# SIM800.net
KiCad netlist of a schematic drawn in Altium Designer
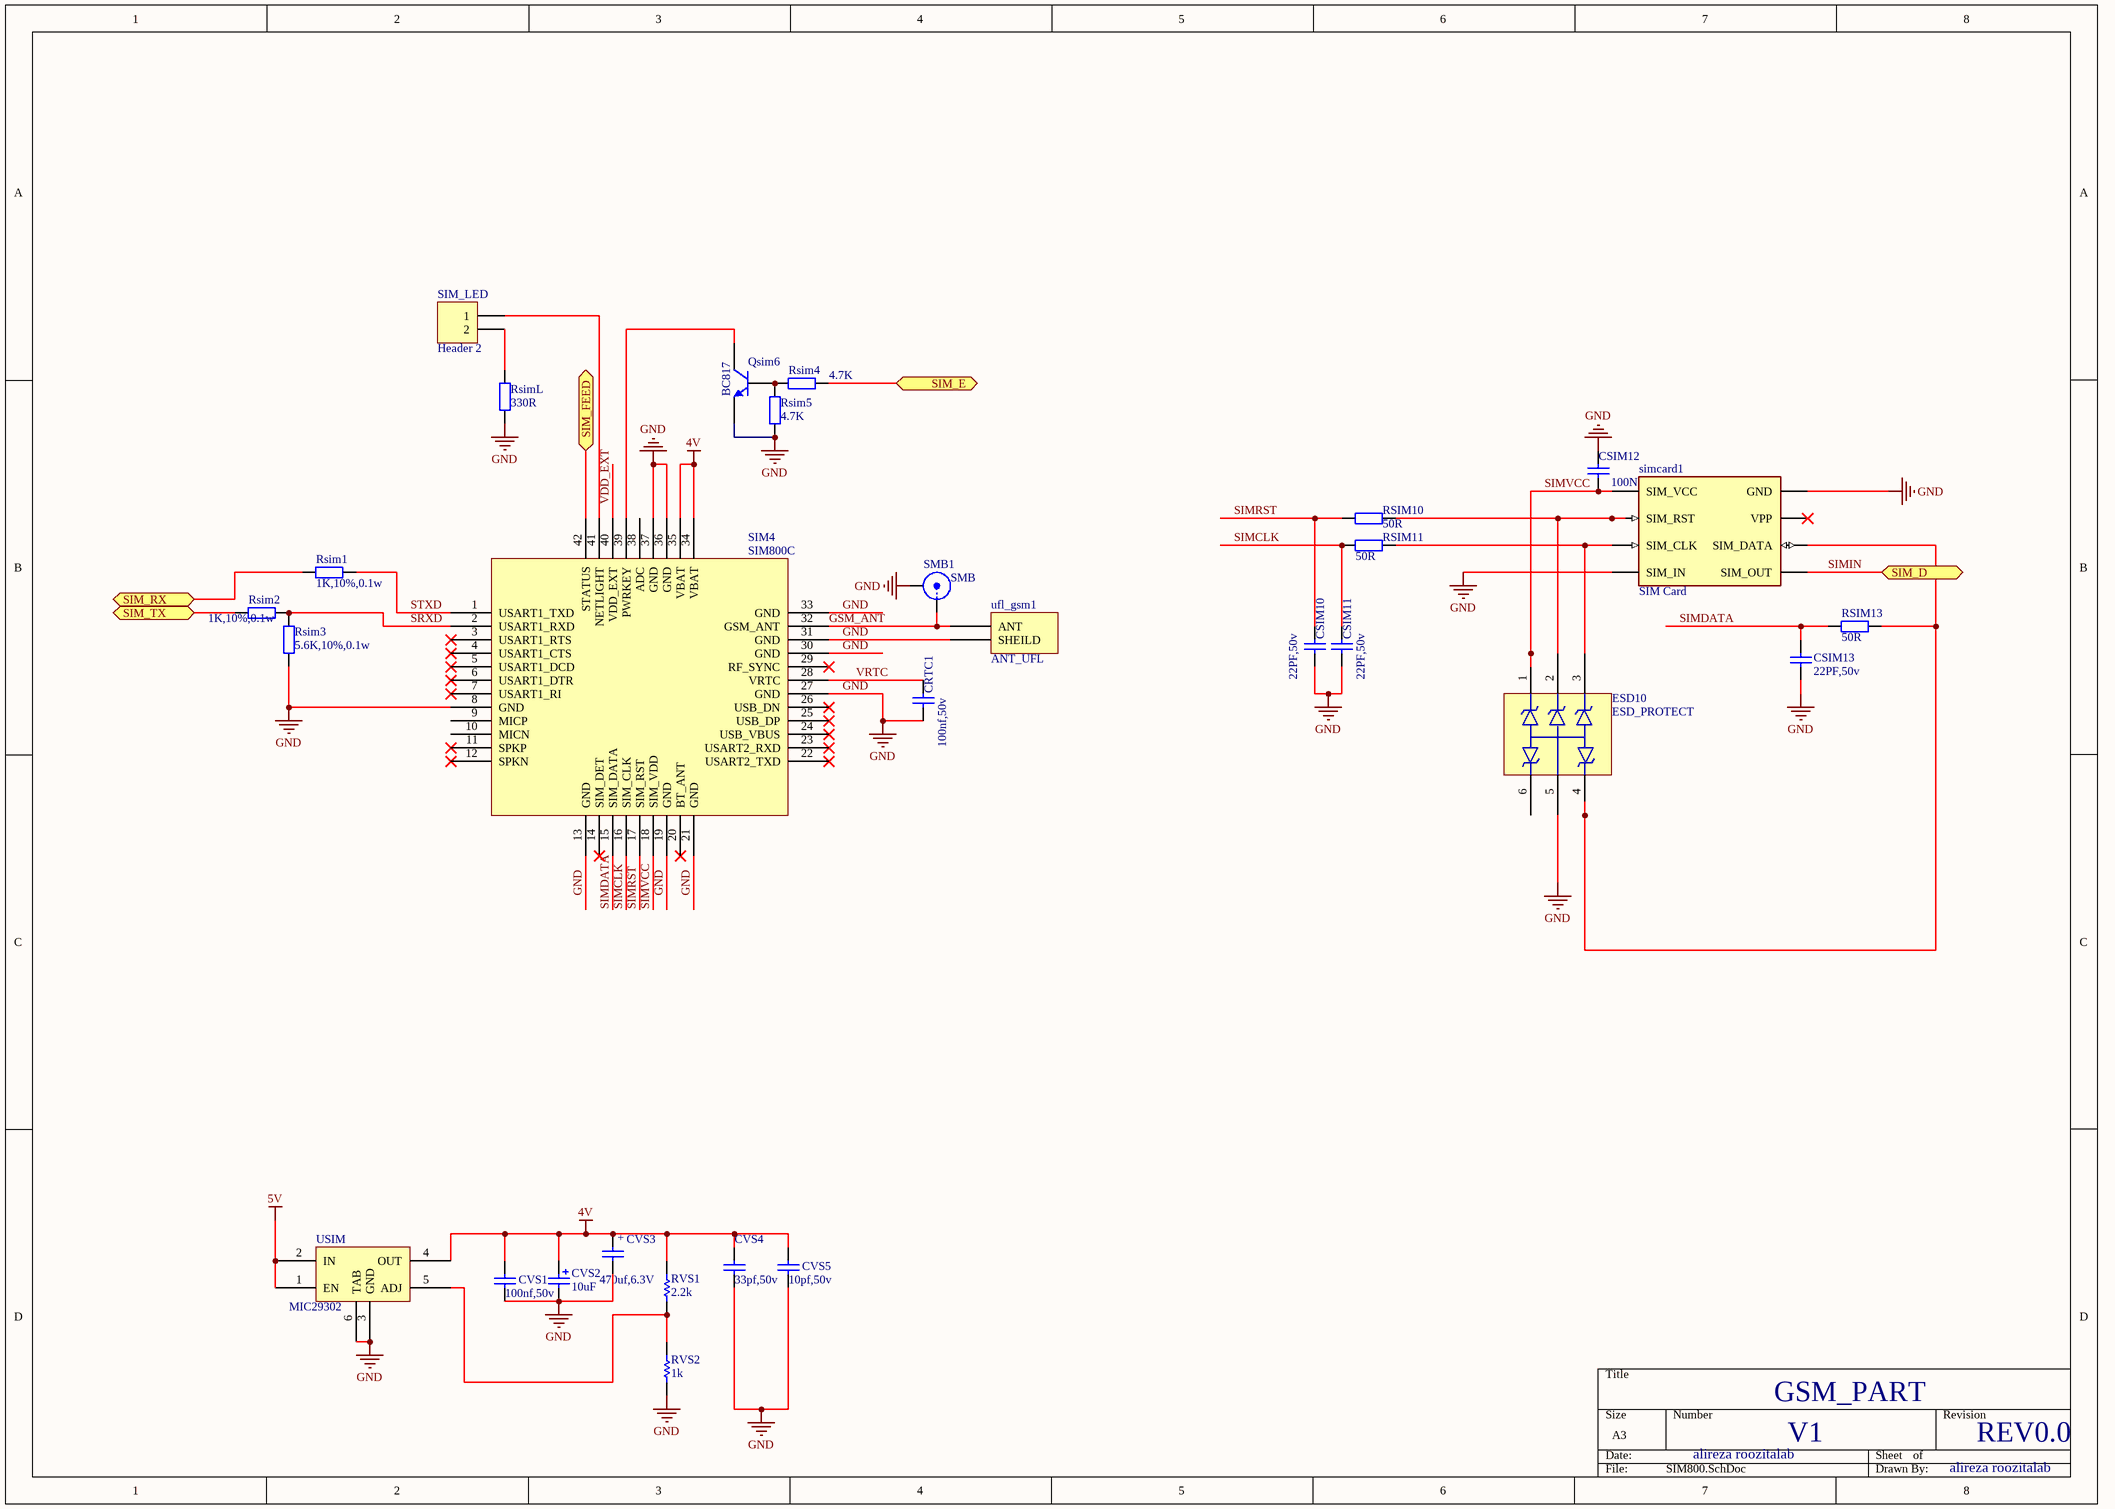
[diagram p0: SIM800.SchDoc]

(export (version "E")
  (design (tool "Eeschema 10.0.6"))
  (components
    (comp (ref "CRTC1")
      (value "100nf,50v")
      (footprint "0805.")
      (description "Capacitor")
      (fields (field (name "PUBLISHER") "Altium Limited"))
      (libsource (lib "MBIO-SCHPCB-MBFD-REV1") (part "Cap"))
    )
    (comp (ref "CSIM10")
      (value "22PF,50v")
      (footprint "0805.")
      (description "Capacitor")
      (fields (field (name "PUBLISHER") "Altium Limited"))
      (libsource (lib "MBIO-SCHPCB-MBFD-REV1") (part "Cap"))
    )
    (comp (ref "CSIM11")
      (value "22PF,50v")
      (footprint "0805.")
      (description "Capacitor")
      (fields (field (name "PUBLISHER") "Altium Limited"))
      (libsource (lib "MBIO-SCHPCB-MBFD-REV1") (part "Cap"))
    )
    (comp (ref "CSIM12")
      (value "100N")
      (footprint "0805.")
      (description "Capacitor")
      (fields (field (name "PUBLISHER") "Altium Limited"))
      (libsource (lib "MBIO-SCHPCB-MBFD-REV1") (part "Cap"))
    )
    (comp (ref "CSIM13")
      (value "22PF,50v")
      (footprint "0805.")
      (description "Capacitor")
      (fields (field (name "PUBLISHER") "Altium Limited"))
      (libsource (lib "MBIO-SCHPCB-MBFD-REV1") (part "Cap"))
    )
    (comp (ref "CVS1")
      (value "100nf,50v")
      (footprint "0805.")
      (description "Capacitor")
      (fields (field (name "PUBLISHER") "Altium Limited"))
      (libsource (lib "MBIO-SCHPCB-MBFD-REV1") (part "Cap"))
    )
    (comp (ref "CVS2")
      (value "10uF")
      (footprint "C1206.")
      (description "Polarized Capacitor (Radial)")
      (fields (field (name "PUBLISHER") "Altium Limited"))
      (libsource (lib "PCB_Project1") (part "Cap Pol1"))
    )
    (comp (ref "CVS3")
      (value "470uf,6.3V")
      (footprint "MY_SMC_D")
      (description "Polar capacitor")
      (fields (field (name "ASID PART NUMBER") "C-AS"))
      (libsource (lib "TPS54331") (part "Cap Pol"))
    )
    (comp (ref "CVS4")
      (value "33pf,50v")
      (footprint "0805.")
      (description "Capacitor")
      (fields (field (name "PUBLISHER") "Altium Limited"))
      (libsource (lib "MBIO-SCHPCB-MBFD-REV1") (part "Cap"))
    )
    (comp (ref "CVS5")
      (value "10pf,50v")
      (footprint "0805.")
      (description "Capacitor")
      (fields (field (name "PUBLISHER") "Altium Limited"))
      (libsource (lib "MBIO-SCHPCB-MBFD-REV1") (part "Cap"))
    )
    (comp (ref "ESD10")
      (value "ESD_PROTECT")
      (footprint "SMF05")
      (libsource (lib "armlib") (part "ESD_PROTECT"))
    )
    (comp (ref "Qsim6")
      (value "BC817")
      (footprint "2N3906_SMD")
      (description "NPN General Purpose Amplifier")
      (fields (field (name "PUBLISHER") "Altium Limited"))
      (libsource (lib "Miscellaneous Devices") (part "2N3904"))
    )
    (comp (ref "Rsim1")
      (value "1K,10%,0.1w")
      (footprint "0805.")
      (description "Resistor")
      (fields (field (name "PUBLISHER") "Altium Limited"))
      (libsource (lib "") (part "Res2_3"))
    )
    (comp (ref "Rsim2")
      (value "1K,10%,0.1w")
      (footprint "0805.")
      (description "Resistor")
      (fields (field (name "PUBLISHER") "Altium Limited"))
      (libsource (lib "") (part "Res2_1"))
    )
    (comp (ref "Rsim3")
      (value "5.6K,10%,0.1w")
      (footprint "0805.")
      (description "Resistor")
      (fields (field (name "PUBLISHER") "Altium Limited"))
      (libsource (lib "MBIO-SCHPCB-MBFD-REV1") (part "Res2"))
    )
    (comp (ref "Rsim4")
      (value "4.7K")
      (footprint "0805.")
      (description "Resistor")
      (fields (field (name "Comment") "10K,10%,0.1w") (field (name "PUBLISHER") "Altium Limited"))
      (libsource (lib "") (part "Res2_2"))
    )
    (comp (ref "Rsim5")
      (value "4.7K")
      (footprint "0805.")
      (description "Resistor")
      (fields (field (name "Comment") "10K,10%,0.1w") (field (name "PUBLISHER") "Altium Limited"))
      (libsource (lib "") (part "Res2_1"))
    )
    (comp (ref "RSIM10")
      (value "50R")
      (footprint "0805.")
      (description "Resistor")
      (fields (field (name "Comment") "47R,10%,0.1w") (field (name "PUBLISHER") "Altium Limited"))
      (libsource (lib "PCB_Project1") (part "Res2"))
    )
    (comp (ref "RSIM11")
      (value "50R")
      (footprint "0805.")
      (description "Resistor")
      (fields (field (name "Comment") "47R,10%,0.1w") (field (name "PUBLISHER") "Altium Limited"))
      (libsource (lib "PCB_Project1") (part "Res2"))
    )
    (comp (ref "RSIM13")
      (value "50R")
      (footprint "0805.")
      (description "Resistor")
      (fields (field (name "Comment") "47R,10%,0.1w") (field (name "PUBLISHER") "Altium Limited"))
      (libsource (lib "PCB_Project1") (part "Res2"))
    )
    (comp (ref "RsimL")
      (value "330R")
      (footprint "0805.")
      (description "Resistor")
      (fields (field (name "Comment") "330R,10%,0.1w") (field (name "PUBLISHER") "Altium Limited"))
      (libsource (lib "") (part "Res2_1"))
    )
    (comp (ref "RVS1")
      (value "2.2k")
      (footprint "0805.")
      (description "Resistor")
      (fields (field (name "PUBLISHER") "Altium Limited"))
      (libsource (lib "PCB_Project1") (part "Res1"))
    )
    (comp (ref "RVS2")
      (value "1k")
      (footprint "0805.")
      (description "Resistor")
      (fields (field (name "PUBLISHER") "Altium Limited"))
      (libsource (lib "PCB_Project1") (part "Res1"))
    )
    (comp (ref "SIM4") (value "SIM800C") (footprint "SIM800C") (libsource (lib "armlib") (part "SIM800C")))
    (comp (ref "simcard1")
      (value "SIM Card")
      (footprint "MY_SIMCARD")
      (description "Sim Card")
      (libsource (lib "Mylib") (part "SIM Card"))
    )
    (comp (ref "SIM_LED")
      (value "Header 2")
      (footprint "HDR1X2")
      (description "Header, 2-Pin")
      (fields (field (name "PUBLISHER") "Altium Limited"))
      (libsource (lib "Miscellaneous Connectors") (part "Header 2"))
    )
    (comp (ref "SMB1")
      (value "SMB")
      (footprint "SMB_V-RJ45")
      (description "SMB Straight Connector")
      (fields (field (name "PUBLISHER") "Altium Limited"))
      (libsource (lib "Miscellaneous Connectors") (part "SMB"))
    )
    (comp (ref "ufl_gsm1")
      (value "ANT_UFL")
      (footprint "UFL_CON")
      (libsource (lib "armlib") (part "ANT_UFL"))
    )
    (comp (ref "USIM") (value "MIC29302") (footprint "MIC29302") (libsource (lib "armlib") (part "MIC29302")))
  )
  (nets
    (net (code "1") (name "/GSM_ANT") (class "Default")
      (node (ref "SIM4") (pin "32") (pinfunction "GSM_ANT_32") (pintype "passive"))
      (node (ref "SMB1") (pin "1") (pinfunction "X_1") (pintype "passive"))
      (node (ref "ufl_gsm1") (pin "2") (pinfunction "ANT_2") (pintype "passive"))
    )
    (net (code "2") (name "/SIMCLK") (class "Default")
      (node (ref "CSIM11") (pin "2") (pinfunction "2_2") (pintype "passive"))
      (node (ref "RSIM11") (pin "1") (pinfunction "1_1") (pintype "passive"))
      (node (ref "SIM4") (pin "16") (pinfunction "SIM_CLK_16") (pintype "passive"))
    )
    (net (code "3") (name "/SIMDATA") (class "Default")
      (node (ref "CSIM13") (pin "2") (pinfunction "2_2") (pintype "passive"))
      (node (ref "RSIM13") (pin "1") (pinfunction "1_1") (pintype "passive"))
      (node (ref "SIM4") (pin "15") (pinfunction "SIM_DATA_15") (pintype "passive"))
    )
    (net (code "4") (name "/SIMIN") (class "Default")
      (node (ref "simcard1") (pin "C8") (pinfunction "SIM_OUT_C8") (pintype "passive"))
    )
    (net (code "5") (name "/SIMRST") (class "Default")
      (node (ref "CSIM10") (pin "2") (pinfunction "2_2") (pintype "passive"))
      (node (ref "RSIM10") (pin "1") (pinfunction "1_1") (pintype "passive"))
      (node (ref "SIM4") (pin "17") (pinfunction "SIM_RST_17") (pintype "passive"))
    )
    (net (code "6") (name "/SIMVCC") (class "Default")
      (node (ref "CSIM12") (pin "1") (pinfunction "1_1") (pintype "passive"))
      (node (ref "ESD10") (pin "1") (pinfunction "1_1") (pintype "passive"))
      (node (ref "SIM4") (pin "18") (pinfunction "SIM_VDD_18") (pintype "passive"))
      (node (ref "simcard1") (pin "C1") (pinfunction "SIM_VCC_C1") (pintype "power_in"))
    )
    (net (code "7") (name "/SIM_E") (class "Default")
      (node (ref "Rsim4") (pin "1") (pinfunction "1_1") (pintype "passive"))
    )
    (net (code "8") (name "/SIM_FEED") (class "Default")
      (node (ref "SIM4") (pin "42") (pinfunction "STATUS_42") (pintype "passive"))
    )
    (net (code "9") (name "/SIM_RX") (class "Default")
      (node (ref "Rsim1") (pin "2") (pinfunction "2_2") (pintype "passive"))
    )
    (net (code "10") (name "/SIM_TX") (class "Default")
      (node (ref "Rsim2") (pin "1") (pinfunction "1_1") (pintype "passive"))
    )
    (net (code "11") (name "/SRXD") (class "Default")
      (node (ref "Rsim2") (pin "2") (pinfunction "2_2") (pintype "passive"))
      (node (ref "Rsim3") (pin "2") (pinfunction "2_2") (pintype "passive"))
      (node (ref "SIM4") (pin "2") (pinfunction "USART1_RXD_2") (pintype "passive"))
    )
    (net (code "12") (name "/STXD") (class "Default")
      (node (ref "Rsim1") (pin "1") (pinfunction "1_1") (pintype "passive"))
      (node (ref "SIM4") (pin "1") (pinfunction "USART1_TXD_1") (pintype "passive"))
    )
    (net (code "13") (name "/VDD_EXT") (class "Default")
      (node (ref "SIM4") (pin "40") (pinfunction "VDD_EXT_40") (pintype "passive"))
    )
    (net (code "14") (name "/VRTC") (class "Default")
      (node (ref "CRTC1") (pin "2") (pinfunction "2_2") (pintype "passive"))
      (node (ref "SIM4") (pin "28") (pinfunction "VRTC_28") (pintype "passive"))
    )
    (net (code "15") (name "4V") (class "Default")
      (node (ref "CVS1") (pin "2") (pinfunction "2_2") (pintype "passive"))
      (node (ref "CVS2") (pin "1") (pinfunction "1_1") (pintype "passive"))
      (node (ref "CVS3") (pin "+") (pinfunction "+_+") (pintype "passive"))
      (node (ref "CVS4") (pin "2") (pinfunction "2_2") (pintype "passive"))
      (node (ref "CVS5") (pin "2") (pinfunction "2_2") (pintype "passive"))
      (node (ref "RVS1") (pin "2") (pinfunction "2_2") (pintype "passive"))
      (node (ref "SIM4") (pin "34") (pinfunction "VBAT_34") (pintype "passive"))
      (node (ref "SIM4") (pin "35") (pinfunction "VBAT_35") (pintype "passive"))
      (node (ref "USIM") (pin "4") (pinfunction "OUT_4") (pintype "passive"))
    )
    (net (code "16") (name "5V") (class "Default")
      (node (ref "USIM") (pin "1") (pinfunction "EN_1") (pintype "passive"))
      (node (ref "USIM") (pin "2") (pinfunction "IN_2") (pintype "passive"))
    )
    (net (code "17") (name "GND") (class "Default")
      (node (ref "CRTC1") (pin "1") (pinfunction "1_1") (pintype "passive"))
      (node (ref "CSIM10") (pin "1") (pinfunction "1_1") (pintype "passive"))
      (node (ref "CSIM11") (pin "1") (pinfunction "1_1") (pintype "passive"))
      (node (ref "CSIM12") (pin "2") (pinfunction "2_2") (pintype "passive"))
      (node (ref "CSIM13") (pin "1") (pinfunction "1_1") (pintype "passive"))
      (node (ref "CVS1") (pin "1") (pinfunction "1_1") (pintype "passive"))
      (node (ref "CVS2") (pin "2") (pinfunction "2_2") (pintype "passive"))
      (node (ref "CVS3") (pin "-") (pinfunction "-_-") (pintype "passive"))
      (node (ref "CVS4") (pin "1") (pinfunction "1_1") (pintype "passive"))
      (node (ref "CVS5") (pin "1") (pinfunction "1_1") (pintype "passive"))
      (node (ref "ESD10") (pin "5") (pinfunction "5_5") (pintype "passive"))
      (node (ref "Qsim6") (pin "1") (pinfunction "E_1") (pintype "passive"))
      (node (ref "RVS2") (pin "1") (pinfunction "1_1") (pintype "passive"))
      (node (ref "Rsim3") (pin "1") (pinfunction "1_1") (pintype "passive"))
      (node (ref "Rsim5") (pin "1") (pinfunction "1_1") (pintype "passive"))
      (node (ref "RsimL") (pin "1") (pinfunction "1_1") (pintype "passive"))
      (node (ref "SIM4") (pin "13") (pinfunction "GND_13") (pintype "passive"))
      (node (ref "SIM4") (pin "19") (pinfunction "GND_19") (pintype "passive"))
      (node (ref "SIM4") (pin "21") (pinfunction "GND_21") (pintype "passive"))
      (node (ref "SIM4") (pin "27") (pinfunction "GND_27") (pintype "passive"))
      (node (ref "SIM4") (pin "30") (pinfunction "GND_30") (pintype "passive"))
      (node (ref "SIM4") (pin "31") (pinfunction "GND_31") (pintype "passive"))
      (node (ref "SIM4") (pin "33") (pinfunction "GND_33") (pintype "passive"))
      (node (ref "SIM4") (pin "36") (pinfunction "GND_36") (pintype "passive"))
      (node (ref "SIM4") (pin "37") (pinfunction "GND_37") (pintype "passive"))
      (node (ref "SIM4") (pin "8") (pinfunction "GND_8") (pintype "passive"))
      (node (ref "SMB1") (pin "2") (pinfunction "Y_2") (pintype "passive"))
      (node (ref "USIM") (pin "3") (pinfunction "GND_3") (pintype "passive"))
      (node (ref "USIM") (pin "6") (pinfunction "TAB_6") (pintype "passive"))
      (node (ref "simcard1") (pin "C4") (pinfunction "SIM_IN_C4") (pintype "passive"))
      (node (ref "simcard1") (pin "C5") (pinfunction "GND_C5") (pintype "power_in"))
      (node (ref "ufl_gsm1") (pin "1") (pinfunction "SHEILD_1") (pintype "passive"))
    )
    (net (code "18") (name "Net-(Qsim6-B)") (class "Default")
      (node (ref "Qsim6") (pin "2") (pinfunction "B_2") (pintype "passive"))
      (node (ref "Rsim4") (pin "2") (pinfunction "2_2") (pintype "passive"))
      (node (ref "Rsim5") (pin "2") (pinfunction "2_2") (pintype "passive"))
    )
    (net (code "19") (name "Net-(Qsim6-C)") (class "Default")
      (node (ref "Qsim6") (pin "3") (pinfunction "C_3") (pintype "passive"))
      (node (ref "SIM4") (pin "39") (pinfunction "PWRKEY_39") (pintype "passive"))
    )
    (net (code "20") (name "Net-(RsimL-Pad2)") (class "Default")
      (node (ref "RsimL") (pin "2") (pinfunction "2_2") (pintype "passive"))
      (node (ref "SIM_LED") (pin "2") (pinfunction "2_2") (pintype "passive"))
    )
    (net (code "21") (name "Net-(SIM4-NETLIGHT)") (class "Default")
      (node (ref "SIM4") (pin "41") (pinfunction "NETLIGHT_41") (pintype "passive"))
      (node (ref "SIM_LED") (pin "1") (pinfunction "1_1") (pintype "passive"))
    )
    (net (code "22") (name "Net-(USIM-ADJ)") (class "Default")
      (node (ref "RVS1") (pin "1") (pinfunction "1_1") (pintype "passive"))
      (node (ref "RVS2") (pin "2") (pinfunction "2_2") (pintype "passive"))
      (node (ref "USIM") (pin "5") (pinfunction "ADJ_5") (pintype "passive"))
    )
    (net (code "23") (name "Net-(simcard1-SIM_CLK)") (class "Default")
      (node (ref "ESD10") (pin "3") (pinfunction "3_3") (pintype "passive"))
      (node (ref "RSIM11") (pin "2") (pinfunction "2_2") (pintype "passive"))
      (node (ref "simcard1") (pin "C3") (pinfunction "SIM_CLK_C3") (pintype "input"))
    )
    (net (code "24") (name "Net-(simcard1-SIM_DATA)") (class "Default")
      (node (ref "ESD10") (pin "4") (pinfunction "4_4") (pintype "passive"))
      (node (ref "RSIM13") (pin "2") (pinfunction "2_2") (pintype "passive"))
      (node (ref "simcard1") (pin "C7") (pinfunction "SIM_DATA_C7") (pintype "bidirectional"))
    )
    (net (code "25") (name "Net-(simcard1-SIM_RST)") (class "Default")
      (node (ref "ESD10") (pin "2") (pinfunction "2_2") (pintype "passive"))
      (node (ref "RSIM10") (pin "2") (pinfunction "2_2") (pintype "passive"))
      (node (ref "simcard1") (pin "C2") (pinfunction "SIM_RST_C2") (pintype "input"))
    )
    (net (code "26") (name "unconnected-(ESD10-Pad6)") (class "Default")
      (node (ref "ESD10") (pin "6") (pinfunction "6_6") (pintype "passive"))
    )
    (net (code "27") (name "unconnected-(SIM4-ADC-Pad38)") (class "Default")
      (node (ref "SIM4") (pin "38") (pinfunction "ADC_38") (pintype "passive"))
    )
    (net (code "28") (name "unconnected-(SIM4-BT_ANT-Pad20)") (class "Default")
      (node (ref "SIM4") (pin "20") (pinfunction "BT_ANT_20") (pintype "passive+no_connect"))
    )
    (net (code "29") (name "unconnected-(SIM4-MICN-Pad10)") (class "Default")
      (node (ref "SIM4") (pin "10") (pinfunction "MICN_10") (pintype "passive"))
    )
    (net (code "30") (name "unconnected-(SIM4-MICP-Pad9)") (class "Default")
      (node (ref "SIM4") (pin "9") (pinfunction "MICP_9") (pintype "passive"))
    )
    (net (code "31") (name "unconnected-(SIM4-RF_SYNC-Pad29)") (class "Default")
      (node (ref "SIM4") (pin "29") (pinfunction "RF_SYNC_29") (pintype "passive+no_connect"))
    )
    (net (code "32") (name "unconnected-(SIM4-SIM_DET-Pad14)") (class "Default")
      (node (ref "SIM4") (pin "14") (pinfunction "SIM_DET_14") (pintype "passive+no_connect"))
    )
    (net (code "33") (name "unconnected-(SIM4-SPKN-Pad12)") (class "Default")
      (node (ref "SIM4") (pin "12") (pinfunction "SPKN_12") (pintype "passive+no_connect"))
    )
    (net (code "34") (name "unconnected-(SIM4-SPKP-Pad11)") (class "Default")
      (node (ref "SIM4") (pin "11") (pinfunction "SPKP_11") (pintype "passive+no_connect"))
    )
    (net (code "35") (name "unconnected-(SIM4-USART1_CTS-Pad4)") (class "Default")
      (node (ref "SIM4") (pin "4") (pinfunction "USART1_CTS_4") (pintype "passive+no_connect"))
    )
    (net (code "36") (name "unconnected-(SIM4-USART1_DCD-Pad5)") (class "Default")
      (node (ref "SIM4") (pin "5") (pinfunction "USART1_DCD_5") (pintype "passive+no_connect"))
    )
    (net (code "37") (name "unconnected-(SIM4-USART1_DTR-Pad6)") (class "Default")
      (node (ref "SIM4") (pin "6") (pinfunction "USART1_DTR_6") (pintype "passive+no_connect"))
    )
    (net (code "38") (name "unconnected-(SIM4-USART1_RI-Pad7)") (class "Default")
      (node (ref "SIM4") (pin "7") (pinfunction "USART1_RI_7") (pintype "passive+no_connect"))
    )
    (net (code "39") (name "unconnected-(SIM4-USART1_RTS-Pad3)") (class "Default")
      (node (ref "SIM4") (pin "3") (pinfunction "USART1_RTS_3") (pintype "passive+no_connect"))
    )
    (net (code "40") (name "unconnected-(SIM4-USART2_RXD-Pad23)") (class "Default")
      (node (ref "SIM4") (pin "23") (pinfunction "USART2_RXD_23") (pintype "passive+no_connect"))
    )
    (net (code "41") (name "unconnected-(SIM4-USART2_TXD-Pad22)") (class "Default")
      (node (ref "SIM4") (pin "22") (pinfunction "USART2_TXD_22") (pintype "passive+no_connect"))
    )
    (net (code "42") (name "unconnected-(SIM4-USB_DN-Pad26)") (class "Default")
      (node (ref "SIM4") (pin "26") (pinfunction "USB_DN_26") (pintype "passive+no_connect"))
    )
    (net (code "43") (name "unconnected-(SIM4-USB_DP-Pad25)") (class "Default")
      (node (ref "SIM4") (pin "25") (pinfunction "USB_DP_25") (pintype "passive+no_connect"))
    )
    (net (code "44") (name "unconnected-(SIM4-USB_VBUS-Pad24)") (class "Default")
      (node (ref "SIM4") (pin "24") (pinfunction "USB_VBUS_24") (pintype "passive+no_connect"))
    )
    (net (code "45") (name "unconnected-(simcard1-VPP-PadC6)") (class "Default")
      (node (ref "simcard1") (pin "C6") (pinfunction "VPP_C6") (pintype "passive+no_connect"))
    )
  )
)
